# Sheet1.net
KiCad netlist of a schematic drawn in Altium Designer
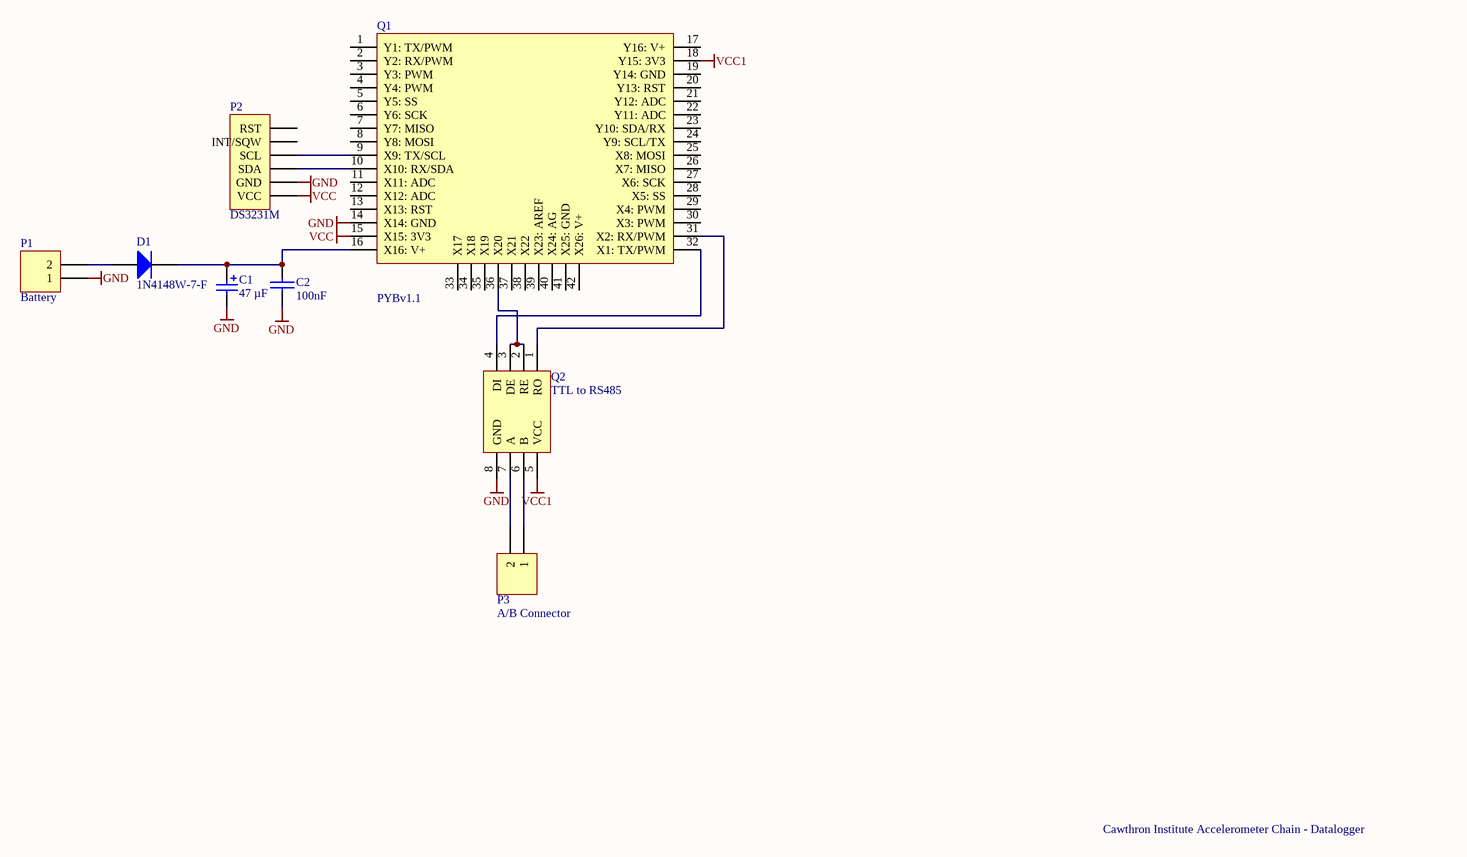
[diagram p0: Sheet1.SchDoc]

(export (version "E")
  (design (tool "Eeschema 10.0.6"))
  (components
    (comp (ref "C1")
      (value "CAP ALUM 22UF 20% 50V SMD")
      (footprint "CAP POL 8x5.4mm SMT")
      (fields
        (field (name "MANUFACTURER") "Nichicon")
        (field (name "MANUFACTURER PART NUMBER") "UWX1V220MCL1GB")
        (field (name "TOLERANCE") "±20%")
        (field (name "CAPACITANCE 1") "47 µF")
      )
      (libsource (lib "EE209V3") (part "SMT-CAP 22uF/35V SM"))
    )
    (comp (ref "C2")
      (value "100nF")
      (footprint "0805 CAP")
      (description "SMT Capacitor Non Polarised")
      (libsource (lib "EE209V3") (part "SMT- Cap"))
    )
    (comp (ref "D1")
      (value "1N4148W-7-F")
      (footprint "SOD123")
      (description "DIODE GEN PURP 100V 300MA SOD123")
      (fields
        (field (name "MANUFACTURER") "Diodes Incorporated")
        (field (name "MANUFACTURER PART NUMBER") "1N4148W-13-F")
      )
      (libsource (lib "EE209V3") (part "SMT-Diode 1N4148W-7-F"))
    )
    (comp (ref "P1")
      (value "Battery")
      (footprint "HDR1X2")
      (description "Header, 2-Pin")
      (fields (field (name "PUBLISHER") "Altium Limited"))
      (libsource (lib "Miscellaneous Connectors") (part "Header 2"))
    )
    (comp (ref "P2")
      (value "DS3231M")
      (footprint "HDR1X6")
      (description "Header, 6-Pin")
      (fields (field (name "PUBLISHER") "Altium Limited"))
      (libsource (lib "Miscellaneous Connectors") (part "Header 6"))
    )
    (comp (ref "P3")
      (value "A/B Connector")
      (footprint "HDR1X2")
      (description "Header, 2-Pin")
      (fields (field (name "PUBLISHER") "Altium Limited"))
      (libsource (lib "") (part "Header 2_1"))
    )
    (comp (ref "Q1")
      (value "PYBv1.1")
      (footprint "PcbLib1:PCBComponent_1")
      (description "Microcontroller")
      (libsource (lib "PYBv1.1") (part "PYBv1.1"))
    )
    (comp (ref "Q2")
      (value "TTL to RS485")
      (footprint "PCBComponent_1")
      (description "Converter")
      (libsource (lib "TTL to RS485") (part "TTL to RS485"))
    )
  )
  (nets
    (net (code "1") (name "GND") (class "Default")
      (node (ref "C1") (pin "2") (pinfunction "2_2") (pintype "passive"))
      (node (ref "C2") (pin "2") (pinfunction "2_2") (pintype "passive"))
      (node (ref "P1") (pin "1") (pinfunction "1_1") (pintype "passive"))
      (node (ref "P2") (pin "5") (pinfunction "GND_5") (pintype "passive"))
      (node (ref "Q1") (pin "14") (pinfunction "X14:_GND_14") (pintype "passive"))
      (node (ref "Q2") (pin "8") (pinfunction "GND_8") (pintype "passive"))
    )
    (net (code "2") (name "Net-(D1-A)") (class "Default")
      (node (ref "D1") (pin "1") (pinfunction "A_1") (pintype "passive"))
      (node (ref "P1") (pin "2") (pinfunction "2_2") (pintype "passive"))
    )
    (net (code "3") (name "Net-(D1-K)") (class "Default")
      (node (ref "C1") (pin "1") (pinfunction "1_1") (pintype "passive"))
      (node (ref "C2") (pin "1") (pinfunction "1_1") (pintype "passive"))
      (node (ref "D1") (pin "2") (pinfunction "K_2") (pintype "passive"))
      (node (ref "Q1") (pin "16") (pinfunction "X16:_V+_16") (pintype "passive"))
    )
    (net (code "4") (name "Net-(P2-SCL)") (class "Default")
      (node (ref "P2") (pin "3") (pinfunction "SCL_3") (pintype "passive"))
      (node (ref "Q1") (pin "9") (pinfunction "X9:_TX/SCL_9") (pintype "passive"))
    )
    (net (code "5") (name "Net-(P2-SDA)") (class "Default")
      (node (ref "P2") (pin "4") (pinfunction "SDA_4") (pintype "passive"))
      (node (ref "Q1") (pin "10") (pinfunction "X10:_RX/SDA_10") (pintype "passive"))
    )
    (net (code "6") (name "Net-(Q1-X1:_TX{slash}PWM)") (class "Default")
      (node (ref "Q1") (pin "32") (pinfunction "X1:_TX/PWM_32") (pintype "passive"))
      (node (ref "Q2") (pin "4") (pinfunction "DI_4") (pintype "passive"))
    )
    (net (code "7") (name "Net-(Q1-X2:_RX{slash}PWM)") (class "Default")
      (node (ref "Q1") (pin "31") (pinfunction "X2:_RX/PWM_31") (pintype "passive"))
      (node (ref "Q2") (pin "1") (pinfunction "RO_1") (pintype "passive"))
    )
    (net (code "8") (name "Net-(Q1-X20)") (class "Default")
      (node (ref "Q1") (pin "36") (pinfunction "X20_36") (pintype "passive"))
      (node (ref "Q2") (pin "2") (pinfunction "RE_2") (pintype "passive"))
      (node (ref "Q2") (pin "3") (pinfunction "DE_3") (pintype "passive"))
    )
    (net (code "9") (name "Net-(Q2-A)") (class "Default")
      (node (ref "P3") (pin "2") (pinfunction "2_2") (pintype "passive"))
      (node (ref "Q2") (pin "7") (pinfunction "A_7") (pintype "passive"))
    )
    (net (code "10") (name "Net-(Q2-B)") (class "Default")
      (node (ref "P3") (pin "1") (pinfunction "1_1") (pintype "passive"))
      (node (ref "Q2") (pin "6") (pinfunction "B_6") (pintype "passive"))
    )
    (net (code "11") (name "VCC") (class "Default")
      (node (ref "P2") (pin "6") (pinfunction "VCC_6") (pintype "passive"))
      (node (ref "Q1") (pin "15") (pinfunction "X15:_3V3_15") (pintype "passive"))
    )
    (net (code "12") (name "VCC1") (class "Default")
      (node (ref "Q1") (pin "18") (pinfunction "Y15:_3V3_18") (pintype "passive"))
      (node (ref "Q2") (pin "5") (pinfunction "VCC_5") (pintype "passive"))
    )
    (net (code "13") (name "unconnected-(P2-INT{slash}SQW-Pad2)") (class "Default")
      (node (ref "P2") (pin "2") (pinfunction "INT/SQW_2") (pintype "passive"))
    )
    (net (code "14") (name "unconnected-(P2-RST-Pad1)") (class "Default")
      (node (ref "P2") (pin "1") (pinfunction "RST_1") (pintype "passive"))
    )
    (net (code "15") (name "unconnected-(Q1-X3:_PWM-Pad30)") (class "Default")
      (node (ref "Q1") (pin "30") (pinfunction "X3:_PWM_30") (pintype "passive"))
    )
    (net (code "16") (name "unconnected-(Q1-X4:_PWM-Pad29)") (class "Default")
      (node (ref "Q1") (pin "29") (pinfunction "X4:_PWM_29") (pintype "passive"))
    )
    (net (code "17") (name "unconnected-(Q1-X5:_SS-Pad28)") (class "Default")
      (node (ref "Q1") (pin "28") (pinfunction "X5:_SS_28") (pintype "passive"))
    )
    (net (code "18") (name "unconnected-(Q1-X6:_SCK-Pad27)") (class "Default")
      (node (ref "Q1") (pin "27") (pinfunction "X6:_SCK_27") (pintype "passive"))
    )
    (net (code "19") (name "unconnected-(Q1-X7:_MISO-Pad26)") (class "Default")
      (node (ref "Q1") (pin "26") (pinfunction "X7:_MISO_26") (pintype "passive"))
    )
    (net (code "20") (name "unconnected-(Q1-X8:_MOSI-Pad25)") (class "Default")
      (node (ref "Q1") (pin "25") (pinfunction "X8:_MOSI_25") (pintype "passive"))
    )
    (net (code "21") (name "unconnected-(Q1-X11:_ADC-Pad11)") (class "Default")
      (node (ref "Q1") (pin "11") (pinfunction "X11:_ADC_11") (pintype "passive"))
    )
    (net (code "22") (name "unconnected-(Q1-X12:_ADC-Pad12)") (class "Default")
      (node (ref "Q1") (pin "12") (pinfunction "X12:_ADC_12") (pintype "passive"))
    )
    (net (code "23") (name "unconnected-(Q1-X13:_RST-Pad13)") (class "Default")
      (node (ref "Q1") (pin "13") (pinfunction "X13:_RST_13") (pintype "passive"))
    )
    (net (code "24") (name "unconnected-(Q1-X17-Pad33)") (class "Default")
      (node (ref "Q1") (pin "33") (pinfunction "X17_33") (pintype "passive"))
    )
    (net (code "25") (name "unconnected-(Q1-X18-Pad34)") (class "Default")
      (node (ref "Q1") (pin "34") (pinfunction "X18_34") (pintype "passive"))
    )
    (net (code "26") (name "unconnected-(Q1-X19-Pad35)") (class "Default")
      (node (ref "Q1") (pin "35") (pinfunction "X19_35") (pintype "passive"))
    )
    (net (code "27") (name "unconnected-(Q1-X21-Pad37)") (class "Default")
      (node (ref "Q1") (pin "37") (pinfunction "X21_37") (pintype "passive"))
    )
    (net (code "28") (name "unconnected-(Q1-X22-Pad38)") (class "Default")
      (node (ref "Q1") (pin "38") (pinfunction "X22_38") (pintype "passive"))
    )
    (net (code "29") (name "unconnected-(Q1-X23:_AREF-Pad39)") (class "Default")
      (node (ref "Q1") (pin "39") (pinfunction "X23:_AREF_39") (pintype "passive"))
    )
    (net (code "30") (name "unconnected-(Q1-X24:_AG-Pad40)") (class "Default")
      (node (ref "Q1") (pin "40") (pinfunction "X24:_AG_40") (pintype "passive"))
    )
    (net (code "31") (name "unconnected-(Q1-X25:_GND-Pad41)") (class "Default")
      (node (ref "Q1") (pin "41") (pinfunction "X25:_GND_41") (pintype "passive"))
    )
    (net (code "32") (name "unconnected-(Q1-X26:_V+-Pad42)") (class "Default")
      (node (ref "Q1") (pin "42") (pinfunction "X26:_V+_42") (pintype "passive"))
    )
    (net (code "33") (name "unconnected-(Q1-Y1:_TX{slash}PWM-Pad1)") (class "Default")
      (node (ref "Q1") (pin "1") (pinfunction "Y1:_TX/PWM_1") (pintype "passive"))
    )
    (net (code "34") (name "unconnected-(Q1-Y2:_RX{slash}PWM-Pad2)") (class "Default")
      (node (ref "Q1") (pin "2") (pinfunction "Y2:_RX/PWM_2") (pintype "passive"))
    )
    (net (code "35") (name "unconnected-(Q1-Y3:_PWM-Pad3)") (class "Default")
      (node (ref "Q1") (pin "3") (pinfunction "Y3:_PWM_3") (pintype "passive"))
    )
    (net (code "36") (name "unconnected-(Q1-Y4:_PWM-Pad4)") (class "Default")
      (node (ref "Q1") (pin "4") (pinfunction "Y4:_PWM_4") (pintype "passive"))
    )
    (net (code "37") (name "unconnected-(Q1-Y5:_SS-Pad5)") (class "Default")
      (node (ref "Q1") (pin "5") (pinfunction "Y5:_SS_5") (pintype "passive"))
    )
    (net (code "38") (name "unconnected-(Q1-Y6:_SCK-Pad6)") (class "Default")
      (node (ref "Q1") (pin "6") (pinfunction "Y6:_SCK_6") (pintype "passive"))
    )
    (net (code "39") (name "unconnected-(Q1-Y7:_MISO-Pad7)") (class "Default")
      (node (ref "Q1") (pin "7") (pinfunction "Y7:_MISO_7") (pintype "passive"))
    )
    (net (code "40") (name "unconnected-(Q1-Y8:_MOSI-Pad8)") (class "Default")
      (node (ref "Q1") (pin "8") (pinfunction "Y8:_MOSI_8") (pintype "passive"))
    )
    (net (code "41") (name "unconnected-(Q1-Y9:_SCL{slash}TX-Pad24)") (class "Default")
      (node (ref "Q1") (pin "24") (pinfunction "Y9:_SCL/TX_24") (pintype "passive"))
    )
    (net (code "42") (name "unconnected-(Q1-Y10:_SDA{slash}RX-Pad23)") (class "Default")
      (node (ref "Q1") (pin "23") (pinfunction "Y10:_SDA/RX_23") (pintype "passive"))
    )
    (net (code "43") (name "unconnected-(Q1-Y11:_ADC-Pad22)") (class "Default")
      (node (ref "Q1") (pin "22") (pinfunction "Y11:_ADC_22") (pintype "passive"))
    )
    (net (code "44") (name "unconnected-(Q1-Y12:_ADC-Pad21)") (class "Default")
      (node (ref "Q1") (pin "21") (pinfunction "Y12:_ADC_21") (pintype "passive"))
    )
    (net (code "45") (name "unconnected-(Q1-Y13:_RST-Pad20)") (class "Default")
      (node (ref "Q1") (pin "20") (pinfunction "Y13:_RST_20") (pintype "passive"))
    )
    (net (code "46") (name "unconnected-(Q1-Y14:_GND-Pad19)") (class "Default")
      (node (ref "Q1") (pin "19") (pinfunction "Y14:_GND_19") (pintype "passive"))
    )
    (net (code "47") (name "unconnected-(Q1-Y16:_V+-Pad17)") (class "Default")
      (node (ref "Q1") (pin "17") (pinfunction "Y16:_V+_17") (pintype "passive"))
    )
  )
)
